# Buck_Converters.net
KiCad netlist of a schematic drawn in Altium Designer
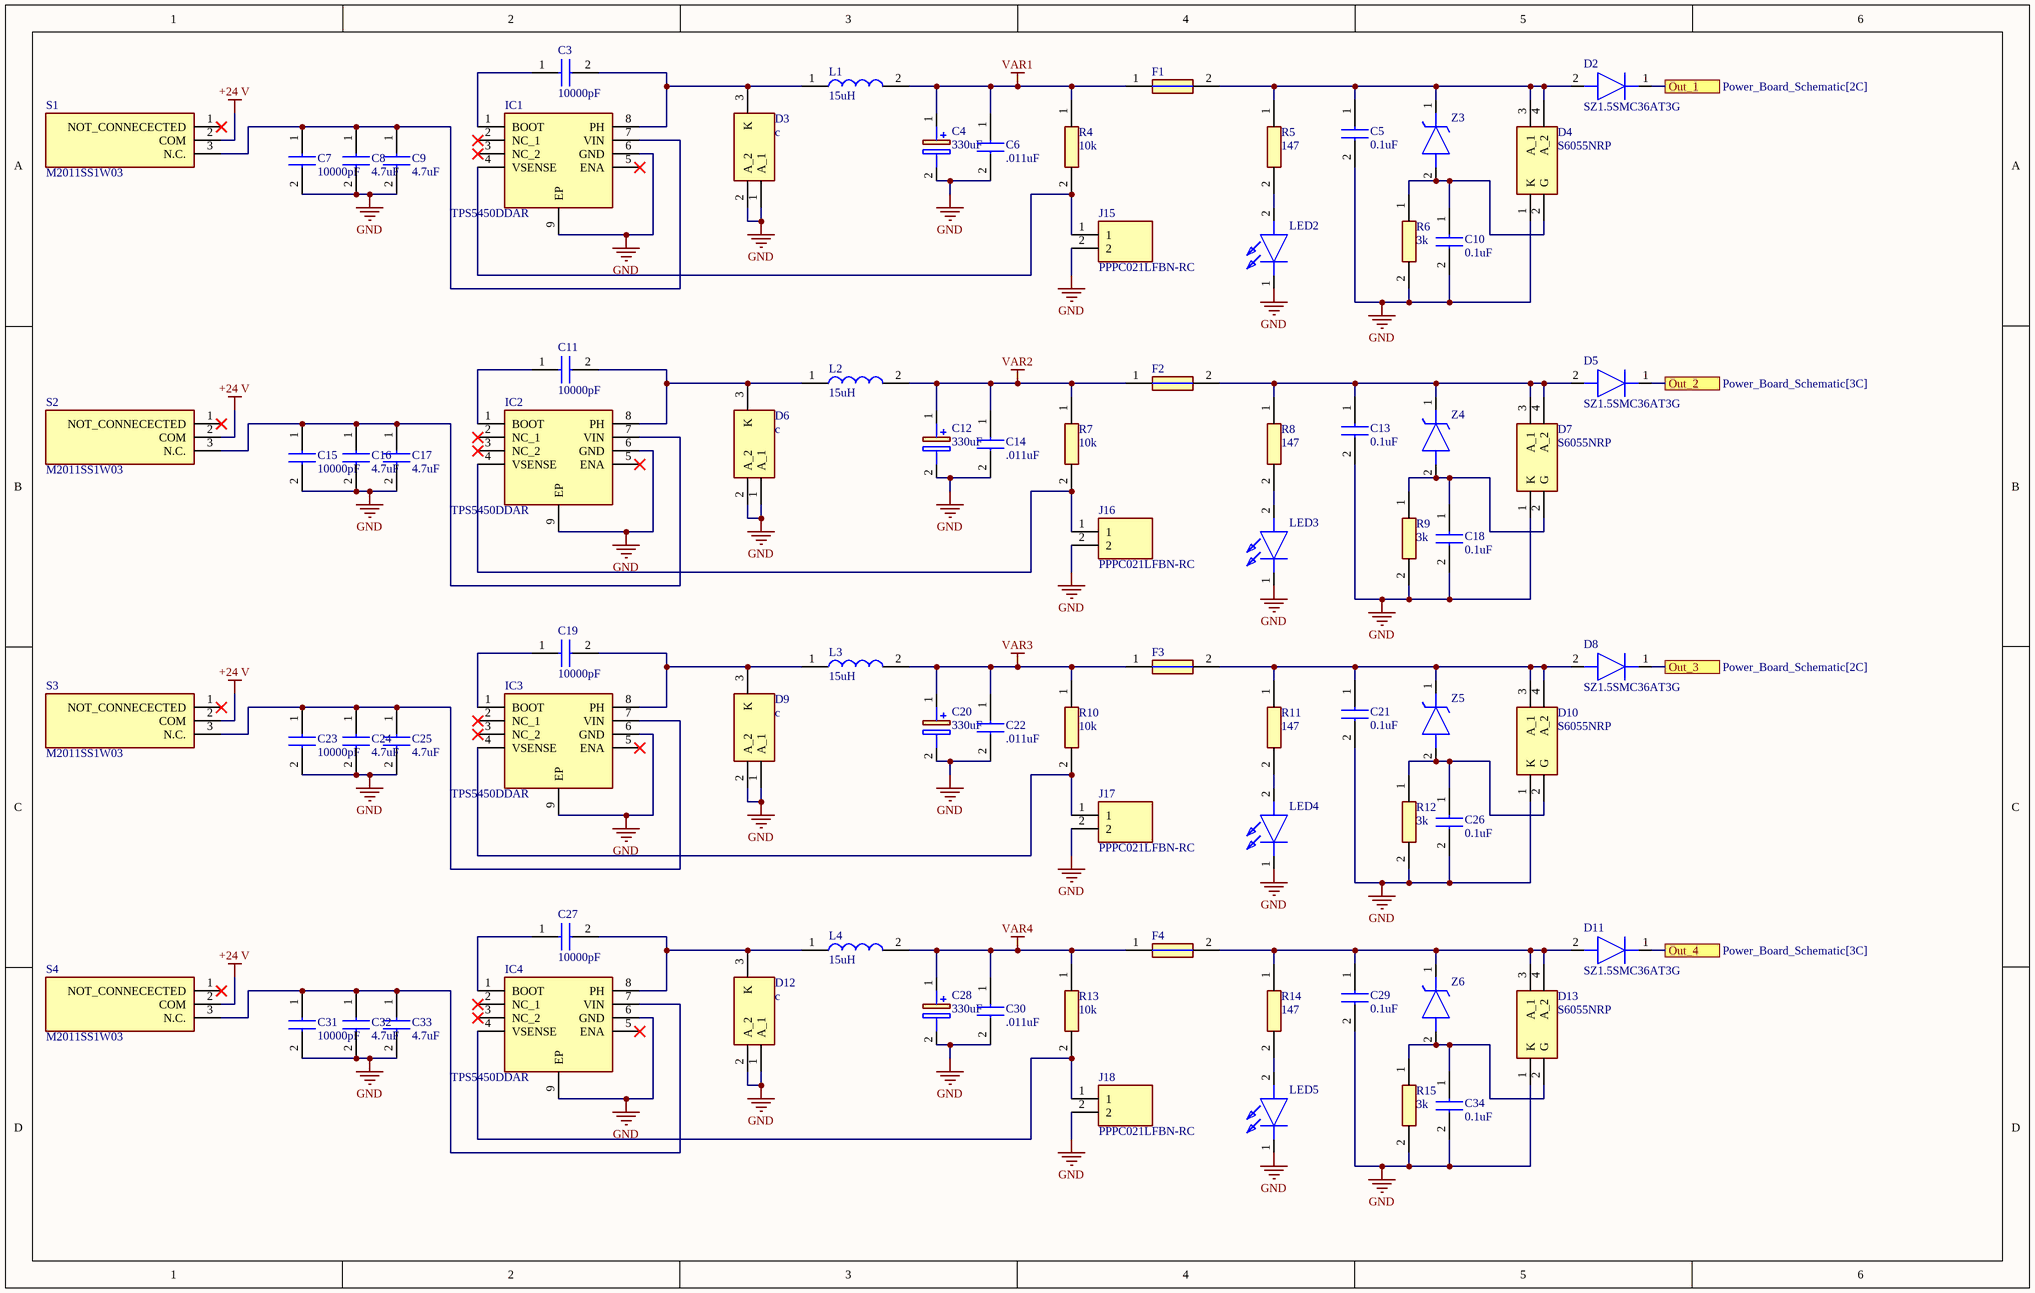
[diagram p0: Buck_Converters.SchDoc]

(export (version "E")
  (design (tool "Eeschema 10.0.6"))
  (components
    (comp (ref "C3")
      (value "10000pF")
      (footprint "SamacSys:CAPC2012X95N")
      (description "Capacitor")
      (fields
        (field (name "MANUFACTURER_PART_NUMBER") "GRM2195C1H103JA01D")
        (field (name "MOUSER PART NUMBER") "81-GRM215C1H103JA01D")
      )
      (libsource (lib "*") (part "GRM2195C1H103JA01D"))
    )
    (comp (ref "C4")
      (value "330uF")
      (footprint "SamacSys:T521X")
      (description "Capacitor Polarised")
      (fields
        (field (name "MANUFACTURER_PART_NUMBER") "T521X337M016ATE025")
        (field (name "MOUSER PART NUMBER") "80-T521X337M16ATE25")
      )
      (libsource (lib "*") (part "T521X337M016ATE025"))
    )
    (comp (ref "C5")
      (value "0.1uF")
      (footprint "SamacSys:CAPC3216X190N")
      (description "Capacitor")
      (fields
        (field (name "MANUFACTURER_PART_NUMBER") "UMJ316BB7104KL8T")
        (field (name "MOUSER PART NUMBER") "963-UMJ316BB7104KL8T")
      )
      (libsource (lib "*") (part "UMJ316BB7104KL8T"))
    )
    (comp (ref "C6")
      (value ".011uF")
      (footprint "SamacSys:CAPC3216X95N")
      (description "Capacitor")
      (fields
        (field (name "MANUFACTURER_PART_NUMBER") "GRM3195C1H113JA01D")
        (field (name "MOUSER PART NUMBER") "81-GRM3195C1H113JA1D")
      )
      (libsource (lib "*") (part "GRM3195C1H113JA01D"))
    )
    (comp (ref "C7")
      (value "10000pF")
      (footprint "SamacSys:CAPC2012X95N")
      (description "Capacitor")
      (fields
        (field (name "MANUFACTURER_PART_NUMBER") "GRM2195C1H103JA01D")
        (field (name "MOUSER PART NUMBER") "81-GRM215C1H103JA01D")
      )
      (libsource (lib "*") (part "GRM2195C1H103JA01D"))
    )
    (comp (ref "C8")
      (value "4.7uF")
      (footprint "SamacSys:CAPC3216X180N")
      (description "Capacitor")
      (fields
        (field (name "MANUFACTURER_PART_NUMBER") "GRM31CR71H475KA12L")
        (field (name "MOUSER PART NUMBER") "81-GRM31CR71H475KA2L")
      )
      (libsource (lib "*") (part "GRM31CR71H475KA12L"))
    )
    (comp (ref "C9")
      (value "4.7uF")
      (footprint "SamacSys:CAPC3216X180N")
      (description "Capacitor")
      (fields
        (field (name "MANUFACTURER_PART_NUMBER") "GRM31CR71H475KA12L")
        (field (name "MOUSER PART NUMBER") "81-GRM31CR71H475KA2L")
      )
      (libsource (lib "*") (part "GRM31CR71H475KA12L"))
    )
    (comp (ref "C10")
      (value "0.1uF")
      (footprint "SamacSys:CAPC3216X190N")
      (description "Capacitor")
      (fields
        (field (name "MANUFACTURER_PART_NUMBER") "UMJ316BB7104KL8T")
        (field (name "MOUSER PART NUMBER") "963-UMJ316BB7104KL8T")
      )
      (libsource (lib "*") (part "UMJ316BB7104KL8T"))
    )
    (comp (ref "C11")
      (value "10000pF")
      (footprint "SamacSys:CAPC2012X95N")
      (description "Capacitor")
      (fields
        (field (name "MANUFACTURER_PART_NUMBER") "GRM2195C1H103JA01D")
        (field (name "MOUSER PART NUMBER") "81-GRM215C1H103JA01D")
      )
      (libsource (lib "*") (part "GRM2195C1H103JA01D"))
    )
    (comp (ref "C12")
      (value "330uF")
      (footprint "SamacSys:T521X")
      (description "Capacitor Polarised")
      (fields
        (field (name "MANUFACTURER_PART_NUMBER") "T521X337M016ATE025")
        (field (name "MOUSER PART NUMBER") "80-T521X337M16ATE25")
      )
      (libsource (lib "*") (part "T521X337M016ATE025"))
    )
    (comp (ref "C13")
      (value "0.1uF")
      (footprint "SamacSys:CAPC3216X190N")
      (description "Capacitor")
      (fields
        (field (name "MANUFACTURER_PART_NUMBER") "UMJ316BB7104KL8T")
        (field (name "MOUSER PART NUMBER") "963-UMJ316BB7104KL8T")
      )
      (libsource (lib "*") (part "UMJ316BB7104KL8T"))
    )
    (comp (ref "C14")
      (value ".011uF")
      (footprint "SamacSys:CAPC3216X95N")
      (description "Capacitor")
      (fields
        (field (name "MANUFACTURER_PART_NUMBER") "GRM3195C1H113JA01D")
        (field (name "MOUSER PART NUMBER") "81-GRM3195C1H113JA1D")
      )
      (libsource (lib "*") (part "GRM3195C1H113JA01D"))
    )
    (comp (ref "C15")
      (value "10000pF")
      (footprint "SamacSys:CAPC2012X95N")
      (description "Capacitor")
      (fields
        (field (name "MANUFACTURER_PART_NUMBER") "GRM2195C1H103JA01D")
        (field (name "MOUSER PART NUMBER") "81-GRM215C1H103JA01D")
      )
      (libsource (lib "*") (part "GRM2195C1H103JA01D"))
    )
    (comp (ref "C16")
      (value "4.7uF")
      (footprint "SamacSys:CAPC3216X180N")
      (description "Capacitor")
      (fields
        (field (name "MANUFACTURER_PART_NUMBER") "GRM31CR71H475KA12L")
        (field (name "MOUSER PART NUMBER") "81-GRM31CR71H475KA2L")
      )
      (libsource (lib "*") (part "GRM31CR71H475KA12L"))
    )
    (comp (ref "C17")
      (value "4.7uF")
      (footprint "SamacSys:CAPC3216X180N")
      (description "Capacitor")
      (fields
        (field (name "MANUFACTURER_PART_NUMBER") "GRM31CR71H475KA12L")
        (field (name "MOUSER PART NUMBER") "81-GRM31CR71H475KA2L")
      )
      (libsource (lib "*") (part "GRM31CR71H475KA12L"))
    )
    (comp (ref "C18")
      (value "0.1uF")
      (footprint "SamacSys:CAPC3216X190N")
      (description "Capacitor")
      (fields
        (field (name "MANUFACTURER_PART_NUMBER") "UMJ316BB7104KL8T")
        (field (name "MOUSER PART NUMBER") "963-UMJ316BB7104KL8T")
      )
      (libsource (lib "*") (part "UMJ316BB7104KL8T"))
    )
    (comp (ref "C19")
      (value "10000pF")
      (footprint "SamacSys:CAPC2012X95N")
      (description "Capacitor")
      (fields
        (field (name "MANUFACTURER_PART_NUMBER") "GRM2195C1H103JA01D")
        (field (name "MOUSER PART NUMBER") "81-GRM215C1H103JA01D")
      )
      (libsource (lib "*") (part "GRM2195C1H103JA01D"))
    )
    (comp (ref "C20")
      (value "330uF")
      (footprint "SamacSys:T521X")
      (description "Capacitor Polarised")
      (fields
        (field (name "MANUFACTURER_PART_NUMBER") "T521X337M016ATE025")
        (field (name "MOUSER PART NUMBER") "80-T521X337M16ATE25")
      )
      (libsource (lib "*") (part "T521X337M016ATE025"))
    )
    (comp (ref "C21")
      (value "0.1uF")
      (footprint "SamacSys:CAPC3216X190N")
      (description "Capacitor")
      (fields
        (field (name "MANUFACTURER_PART_NUMBER") "UMJ316BB7104KL8T")
        (field (name "MOUSER PART NUMBER") "963-UMJ316BB7104KL8T")
      )
      (libsource (lib "*") (part "UMJ316BB7104KL8T"))
    )
    (comp (ref "C22")
      (value ".011uF")
      (footprint "SamacSys:CAPC3216X95N")
      (description "Capacitor")
      (fields
        (field (name "MANUFACTURER_PART_NUMBER") "GRM3195C1H113JA01D")
        (field (name "MOUSER PART NUMBER") "81-GRM3195C1H113JA1D")
      )
      (libsource (lib "*") (part "GRM3195C1H113JA01D"))
    )
    (comp (ref "C23")
      (value "10000pF")
      (footprint "SamacSys:CAPC2012X95N")
      (description "Capacitor")
      (fields
        (field (name "MANUFACTURER_PART_NUMBER") "GRM2195C1H103JA01D")
        (field (name "MOUSER PART NUMBER") "81-GRM215C1H103JA01D")
      )
      (libsource (lib "*") (part "GRM2195C1H103JA01D"))
    )
    (comp (ref "C24")
      (value "4.7uF")
      (footprint "SamacSys:CAPC3216X180N")
      (description "Capacitor")
      (fields
        (field (name "MANUFACTURER_PART_NUMBER") "GRM31CR71H475KA12L")
        (field (name "MOUSER PART NUMBER") "81-GRM31CR71H475KA2L")
      )
      (libsource (lib "*") (part "GRM31CR71H475KA12L"))
    )
    (comp (ref "C25")
      (value "4.7uF")
      (footprint "SamacSys:CAPC3216X180N")
      (description "Capacitor")
      (fields
        (field (name "MANUFACTURER_PART_NUMBER") "GRM31CR71H475KA12L")
        (field (name "MOUSER PART NUMBER") "81-GRM31CR71H475KA2L")
      )
      (libsource (lib "*") (part "GRM31CR71H475KA12L"))
    )
    (comp (ref "C26")
      (value "0.1uF")
      (footprint "SamacSys:CAPC3216X190N")
      (description "Capacitor")
      (fields
        (field (name "MANUFACTURER_PART_NUMBER") "UMJ316BB7104KL8T")
        (field (name "MOUSER PART NUMBER") "963-UMJ316BB7104KL8T")
      )
      (libsource (lib "*") (part "UMJ316BB7104KL8T"))
    )
    (comp (ref "C27")
      (value "10000pF")
      (footprint "SamacSys:CAPC2012X95N")
      (description "Capacitor")
      (fields
        (field (name "MANUFACTURER_PART_NUMBER") "GRM2195C1H103JA01D")
        (field (name "MOUSER PART NUMBER") "81-GRM215C1H103JA01D")
      )
      (libsource (lib "*") (part "GRM2195C1H103JA01D"))
    )
    (comp (ref "C28")
      (value "330uF")
      (footprint "SamacSys:T521X")
      (description "Capacitor Polarised")
      (fields
        (field (name "MANUFACTURER_PART_NUMBER") "T521X337M016ATE025")
        (field (name "MOUSER PART NUMBER") "80-T521X337M16ATE25")
      )
      (libsource (lib "*") (part "T521X337M016ATE025"))
    )
    (comp (ref "C29")
      (value "0.1uF")
      (footprint "SamacSys:CAPC3216X190N")
      (description "Capacitor")
      (fields
        (field (name "MANUFACTURER_PART_NUMBER") "UMJ316BB7104KL8T")
        (field (name "MOUSER PART NUMBER") "963-UMJ316BB7104KL8T")
      )
      (libsource (lib "*") (part "UMJ316BB7104KL8T"))
    )
    (comp (ref "C30")
      (value ".011uF")
      (footprint "SamacSys:CAPC3216X95N")
      (description "Capacitor")
      (fields
        (field (name "MANUFACTURER_PART_NUMBER") "GRM3195C1H113JA01D")
        (field (name "MOUSER PART NUMBER") "81-GRM3195C1H113JA1D")
      )
      (libsource (lib "*") (part "GRM3195C1H113JA01D"))
    )
    (comp (ref "C31")
      (value "10000pF")
      (footprint "SamacSys:CAPC2012X95N")
      (description "Capacitor")
      (fields
        (field (name "MANUFACTURER_PART_NUMBER") "GRM2195C1H103JA01D")
        (field (name "MOUSER PART NUMBER") "81-GRM215C1H103JA01D")
      )
      (libsource (lib "*") (part "GRM2195C1H103JA01D"))
    )
    (comp (ref "C32")
      (value "4.7uF")
      (footprint "SamacSys:CAPC3216X180N")
      (description "Capacitor")
      (fields
        (field (name "MANUFACTURER_PART_NUMBER") "GRM31CR71H475KA12L")
        (field (name "MOUSER PART NUMBER") "81-GRM31CR71H475KA2L")
      )
      (libsource (lib "*") (part "GRM31CR71H475KA12L"))
    )
    (comp (ref "C33")
      (value "4.7uF")
      (footprint "SamacSys:CAPC3216X180N")
      (description "Capacitor")
      (fields
        (field (name "MANUFACTURER_PART_NUMBER") "GRM31CR71H475KA12L")
        (field (name "MOUSER PART NUMBER") "81-GRM31CR71H475KA2L")
      )
      (libsource (lib "*") (part "GRM31CR71H475KA12L"))
    )
    (comp (ref "C34")
      (value "0.1uF")
      (footprint "SamacSys:CAPC3216X190N")
      (description "Capacitor")
      (fields
        (field (name "MANUFACTURER_PART_NUMBER") "UMJ316BB7104KL8T")
        (field (name "MOUSER PART NUMBER") "963-UMJ316BB7104KL8T")
      )
      (libsource (lib "*") (part "UMJ316BB7104KL8T"))
    )
    (comp (ref "D2")
      (value "SZ1.5SMC36AT3G")
      (footprint "SamacSys:DIOM7958X256N")
      (description "Diode")
      (fields (field (name "MOUSER PART NUMBER") "863-SZ1.5SMC36AT3G"))
      (libsource (lib "SamacSys") (part "SZ1.5SMC36AT3G"))
    )
    (comp (ref "D3")
      (value "c")
      (footprint "SamacSys:PMEG045T100EPEZ")
      (description "Schottky Diode")
      (fields
        (field (name "MANUFACTURER_PART_NUMBER") "PMEG045T100EPEZ")
        (field (name "MOUSER PART NUMBER") "771-PMEG045T100EPEZ")
      )
      (libsource (lib "*") (part "PMEG045T100EPEZ"))
    )
    (comp (ref "D4")
      (value "S6055NRP")
      (footprint "SamacSys:S6055NRP")
      (description "SCR")
      (fields (field (name "MOUSER PART NUMBER") "576-S6055NRP"))
      (libsource (lib "*") (part "S6055NRP"))
    )
    (comp (ref "D5")
      (value "SZ1.5SMC36AT3G")
      (footprint "SamacSys:DIOM7958X256N")
      (description "Diode")
      (fields (field (name "MOUSER PART NUMBER") "863-SZ1.5SMC36AT3G"))
      (libsource (lib "SamacSys") (part "SZ1.5SMC36AT3G"))
    )
    (comp (ref "D6")
      (value "c")
      (footprint "SamacSys:PMEG045T100EPEZ")
      (description "Schottky Diode")
      (fields
        (field (name "MANUFACTURER_PART_NUMBER") "PMEG045T100EPEZ")
        (field (name "MOUSER PART NUMBER") "771-PMEG045T100EPEZ")
      )
      (libsource (lib "*") (part "PMEG045T100EPEZ"))
    )
    (comp (ref "D7")
      (value "S6055NRP")
      (footprint "SamacSys:S6055NRP")
      (description "SCR")
      (fields (field (name "MOUSER PART NUMBER") "576-S6055NRP"))
      (libsource (lib "*") (part "S6055NRP"))
    )
    (comp (ref "D8")
      (value "SZ1.5SMC36AT3G")
      (footprint "SamacSys:DIOM7958X256N")
      (description "Diode")
      (fields (field (name "MOUSER PART NUMBER") "863-SZ1.5SMC36AT3G"))
      (libsource (lib "SamacSys") (part "SZ1.5SMC36AT3G"))
    )
    (comp (ref "D9")
      (value "c")
      (footprint "SamacSys:PMEG045T100EPEZ")
      (description "Schottky Diode")
      (fields
        (field (name "MANUFACTURER_PART_NUMBER") "PMEG045T100EPEZ")
        (field (name "MOUSER PART NUMBER") "771-PMEG045T100EPEZ")
      )
      (libsource (lib "*") (part "PMEG045T100EPEZ"))
    )
    (comp (ref "D10")
      (value "S6055NRP")
      (footprint "SamacSys:S6055NRP")
      (description "SCR")
      (fields (field (name "MOUSER PART NUMBER") "576-S6055NRP"))
      (libsource (lib "*") (part "S6055NRP"))
    )
    (comp (ref "D11")
      (value "SZ1.5SMC36AT3G")
      (footprint "SamacSys:DIOM7958X256N")
      (description "Diode")
      (fields (field (name "MOUSER PART NUMBER") "863-SZ1.5SMC36AT3G"))
      (libsource (lib "SamacSys") (part "SZ1.5SMC36AT3G"))
    )
    (comp (ref "D12")
      (value "c")
      (footprint "SamacSys:PMEG045T100EPEZ")
      (description "Schottky Diode")
      (fields
        (field (name "MANUFACTURER_PART_NUMBER") "PMEG045T100EPEZ")
        (field (name "MOUSER PART NUMBER") "771-PMEG045T100EPEZ")
      )
      (libsource (lib "*") (part "PMEG045T100EPEZ"))
    )
    (comp (ref "D13")
      (value "S6055NRP")
      (footprint "SamacSys:S6055NRP")
      (description "SCR")
      (fields (field (name "MOUSER PART NUMBER") "576-S6055NRP"))
      (libsource (lib "*") (part "S6055NRP"))
    )
    (comp (ref "F1")
      (value "MFU0805FF05000P100")
      (footprint "SamacSys:FUSC2012X55N")
      (description "Fuse")
      (fields (field (name "MOUSER PART NUMBER") "594-MFU0805FF05000P1"))
      (libsource (lib "*") (part "MFU0805FF05000P100"))
    )
    (comp (ref "F2")
      (value "MFU0805FF05000P100")
      (footprint "SamacSys:FUSC2012X55N")
      (description "Fuse")
      (fields (field (name "MOUSER PART NUMBER") "594-MFU0805FF05000P1"))
      (libsource (lib "*") (part "MFU0805FF05000P100"))
    )
    (comp (ref "F3")
      (value "MFU0805FF05000P100")
      (footprint "SamacSys:FUSC2012X55N")
      (description "Fuse")
      (fields (field (name "MOUSER PART NUMBER") "594-MFU0805FF05000P1"))
      (libsource (lib "*") (part "MFU0805FF05000P100"))
    )
    (comp (ref "F4")
      (value "MFU0805FF05000P100")
      (footprint "SamacSys:FUSC2012X55N")
      (description "Fuse")
      (fields (field (name "MOUSER PART NUMBER") "594-MFU0805FF05000P1"))
      (libsource (lib "*") (part "MFU0805FF05000P100"))
    )
    (comp (ref "IC1")
      (value "TPS5450DDAR")
      (footprint "SamacSys:SOIC127P600X170-9N")
      (description "Integrated Circuit")
      (fields (field (name "MOUSER PART NUMBER") "595-TPS5450DDAR"))
      (libsource (lib "*") (part "TPS5450DDAR"))
    )
    (comp (ref "IC2")
      (value "TPS5450DDAR")
      (footprint "SamacSys:SOIC127P600X170-9N")
      (description "Integrated Circuit")
      (fields (field (name "MOUSER PART NUMBER") "595-TPS5450DDAR"))
      (libsource (lib "*") (part "TPS5450DDAR"))
    )
    (comp (ref "IC3")
      (value "TPS5450DDAR")
      (footprint "SamacSys:SOIC127P600X170-9N")
      (description "Integrated Circuit")
      (fields (field (name "MOUSER PART NUMBER") "595-TPS5450DDAR"))
      (libsource (lib "*") (part "TPS5450DDAR"))
    )
    (comp (ref "IC4")
      (value "TPS5450DDAR")
      (footprint "SamacSys:SOIC127P600X170-9N")
      (description "Integrated Circuit")
      (fields (field (name "MOUSER PART NUMBER") "595-TPS5450DDAR"))
      (libsource (lib "*") (part "TPS5450DDAR"))
    )
    (comp (ref "J15")
      (value "PPPC021LFBN-RC")
      (footprint "SamacSys:RHDR2W80P0X254_1X2_558X254X850P")
      (description "Connector")
      (libsource (lib "*") (part "PPPC021LFBN-RC"))
    )
    (comp (ref "J16")
      (value "PPPC021LFBN-RC")
      (footprint "SamacSys:RHDR2W80P0X254_1X2_558X254X850P")
      (description "Connector")
      (libsource (lib "*") (part "PPPC021LFBN-RC"))
    )
    (comp (ref "J17")
      (value "PPPC021LFBN-RC")
      (footprint "SamacSys:RHDR2W80P0X254_1X2_558X254X850P")
      (description "Connector")
      (libsource (lib "*") (part "PPPC021LFBN-RC"))
    )
    (comp (ref "J18")
      (value "PPPC021LFBN-RC")
      (footprint "SamacSys:RHDR2W80P0X254_1X2_558X254X850P")
      (description "Connector")
      (libsource (lib "*") (part "PPPC021LFBN-RC"))
    )
    (comp (ref "L1")
      (value "15uH")
      (footprint "SamacSys:WE-PD_1260/1245/1280/121054")
      (description "Inductor")
      (fields
        (field (name "MANUFACTURER_PART_NUMBER") "7447709150")
        (field (name "MOUSER PART NUMBER") "710-7447709150")
      )
      (libsource (lib "*") (part "7447709150"))
    )
    (comp (ref "L2")
      (value "15uH")
      (footprint "SamacSys:WE-PD_1260/1245/1280/121054")
      (description "Inductor")
      (fields
        (field (name "MANUFACTURER_PART_NUMBER") "7447709150")
        (field (name "MOUSER PART NUMBER") "710-7447709150")
      )
      (libsource (lib "*") (part "7447709150"))
    )
    (comp (ref "L3")
      (value "15uH")
      (footprint "SamacSys:WE-PD_1260/1245/1280/121054")
      (description "Inductor")
      (fields
        (field (name "MANUFACTURER_PART_NUMBER") "7447709150")
        (field (name "MOUSER PART NUMBER") "710-7447709150")
      )
      (libsource (lib "*") (part "7447709150"))
    )
    (comp (ref "L4")
      (value "15uH")
      (footprint "SamacSys:WE-PD_1260/1245/1280/121054")
      (description "Inductor")
      (fields
        (field (name "MANUFACTURER_PART_NUMBER") "7447709150")
        (field (name "MOUSER PART NUMBER") "710-7447709150")
      )
      (libsource (lib "*") (part "7447709150"))
    )
    (comp (ref "LED2")
      (value "CMD15-21VYC_TR8")
      (footprint "SamacSys:LEDC3215X130N")
      (description "LED")
      (fields
        (field (name "MANUFACTURER_PART_NUMBER") "CMD15-21VYC/TR8")
        (field (name "MOUSER PART NUMBER") "606-CMD15-21VYC")
      )
      (libsource (lib "*") (part "CMD15-21VYC_TR8"))
    )
    (comp (ref "LED3")
      (value "CMD15-21VYC_TR8")
      (footprint "SamacSys:LEDC3215X130N")
      (description "LED")
      (fields
        (field (name "MANUFACTURER_PART_NUMBER") "CMD15-21VYC/TR8")
        (field (name "MOUSER PART NUMBER") "606-CMD15-21VYC")
      )
      (libsource (lib "*") (part "CMD15-21VYC_TR8"))
    )
    (comp (ref "LED4")
      (value "CMD15-21VYC_TR8")
      (footprint "SamacSys:LEDC3215X130N")
      (description "LED")
      (fields
        (field (name "MANUFACTURER_PART_NUMBER") "CMD15-21VYC/TR8")
        (field (name "MOUSER PART NUMBER") "606-CMD15-21VYC")
      )
      (libsource (lib "*") (part "CMD15-21VYC_TR8"))
    )
    (comp (ref "LED5")
      (value "CMD15-21VYC_TR8")
      (footprint "SamacSys:LEDC3215X130N")
      (description "LED")
      (fields
        (field (name "MANUFACTURER_PART_NUMBER") "CMD15-21VYC/TR8")
        (field (name "MOUSER PART NUMBER") "606-CMD15-21VYC")
      )
      (libsource (lib "*") (part "CMD15-21VYC_TR8"))
    )
    (comp (ref "R4")
      (value "10k")
      (footprint "SamacSys:ERJP08_(1206)")
      (description "Resistor")
      (fields
        (field (name "MANUFACTURER_PART_NUMBER") "ERJ-P08J103V")
        (field (name "MOUSER PART NUMBER") "667-ERJ-P08J103V")
      )
      (libsource (lib "*") (part "ERJ-P08J103V"))
    )
    (comp (ref "R5")
      (value "147")
      (footprint "SamacSys:RESC3216X70N")
      (description "Resistor")
      (fields (field (name "MANUFACTURER_PART_NUMBER") "RK73H2BTTD1470F"))
      (libsource (lib "*") (part "RK73H2BTTD1470F"))
    )
    (comp (ref "R6")
      (value "3k")
      (footprint "SamacSys:ERJP08_(1206)")
      (description "Resistor")
      (fields
        (field (name "MANUFACTURER_PART_NUMBER") "ERJ-P08J302V")
        (field (name "MOUSER PART NUMBER") "667-ERJ-P08J302V")
      )
      (libsource (lib "*") (part "ERJ-P08J302V"))
    )
    (comp (ref "R7")
      (value "10k")
      (footprint "SamacSys:ERJP08_(1206)")
      (description "Resistor")
      (fields
        (field (name "MANUFACTURER_PART_NUMBER") "ERJ-P08J103V")
        (field (name "MOUSER PART NUMBER") "667-ERJ-P08J103V")
      )
      (libsource (lib "*") (part "ERJ-P08J103V"))
    )
    (comp (ref "R8")
      (value "147")
      (footprint "SamacSys:RESC3216X70N")
      (description "Resistor")
      (fields (field (name "MANUFACTURER_PART_NUMBER") "RK73H2BTTD1470F"))
      (libsource (lib "*") (part "RK73H2BTTD1470F"))
    )
    (comp (ref "R9")
      (value "3k")
      (footprint "SamacSys:ERJP08_(1206)")
      (description "Resistor")
      (fields
        (field (name "MANUFACTURER_PART_NUMBER") "ERJ-P08J302V")
        (field (name "MOUSER PART NUMBER") "667-ERJ-P08J302V")
      )
      (libsource (lib "*") (part "ERJ-P08J302V"))
    )
    (comp (ref "R10")
      (value "10k")
      (footprint "SamacSys:ERJP08_(1206)")
      (description "Resistor")
      (fields
        (field (name "MANUFACTURER_PART_NUMBER") "ERJ-P08J103V")
        (field (name "MOUSER PART NUMBER") "667-ERJ-P08J103V")
      )
      (libsource (lib "*") (part "ERJ-P08J103V"))
    )
    (comp (ref "R11")
      (value "147")
      (footprint "SamacSys:RESC3216X70N")
      (description "Resistor")
      (fields (field (name "MANUFACTURER_PART_NUMBER") "RK73H2BTTD1470F"))
      (libsource (lib "*") (part "RK73H2BTTD1470F"))
    )
    (comp (ref "R12")
      (value "3k")
      (footprint "SamacSys:ERJP08_(1206)")
      (description "Resistor")
      (fields
        (field (name "MANUFACTURER_PART_NUMBER") "ERJ-P08J302V")
        (field (name "MOUSER PART NUMBER") "667-ERJ-P08J302V")
      )
      (libsource (lib "*") (part "ERJ-P08J302V"))
    )
    (comp (ref "R13")
      (value "10k")
      (footprint "SamacSys:ERJP08_(1206)")
      (description "Resistor")
      (fields
        (field (name "MANUFACTURER_PART_NUMBER") "ERJ-P08J103V")
        (field (name "MOUSER PART NUMBER") "667-ERJ-P08J103V")
      )
      (libsource (lib "*") (part "ERJ-P08J103V"))
    )
    (comp (ref "R14")
      (value "147")
      (footprint "SamacSys:RESC3216X70N")
      (description "Resistor")
      (fields (field (name "MANUFACTURER_PART_NUMBER") "RK73H2BTTD1470F"))
      (libsource (lib "*") (part "RK73H2BTTD1470F"))
    )
    (comp (ref "R15")
      (value "3k")
      (footprint "SamacSys:ERJP08_(1206)")
      (description "Resistor")
      (fields
        (field (name "MANUFACTURER_PART_NUMBER") "ERJ-P08J302V")
        (field (name "MOUSER PART NUMBER") "667-ERJ-P08J302V")
      )
      (libsource (lib "*") (part "ERJ-P08J302V"))
    )
    (comp (ref "S1")
      (value "M2011SS1W03")
      (footprint "SamacSys:M2011SS1W03")
      (description "Switch")
      (fields (field (name "MOUSER PART NUMBER") "633-M2011SS1W03"))
      (libsource (lib "*") (part "M2011SS1W03"))
    )
    (comp (ref "S2")
      (value "M2011SS1W03")
      (footprint "SamacSys:M2011SS1W03")
      (description "Switch")
      (fields (field (name "MOUSER PART NUMBER") "633-M2011SS1W03"))
      (libsource (lib "*") (part "M2011SS1W03"))
    )
    (comp (ref "S3")
      (value "M2011SS1W03")
      (footprint "SamacSys:M2011SS1W03")
      (description "Switch")
      (fields (field (name "MOUSER PART NUMBER") "633-M2011SS1W03"))
      (libsource (lib "*") (part "M2011SS1W03"))
    )
    (comp (ref "S4")
      (value "M2011SS1W03")
      (footprint "SamacSys:M2011SS1W03")
      (description "Switch")
      (fields (field (name "MOUSER PART NUMBER") "633-M2011SS1W03"))
      (libsource (lib "*") (part "M2011SS1W03"))
    )
    (comp (ref "Z3")
      (value "SMBJ5352B-TP")
      (footprint "SamacSys:DIOM5336X262N")
      (description "Zener Diode")
      (fields (field (name "MOUSER PART NUMBER") "833-SMBJ5352B-TP"))
      (libsource (lib "*") (part "SMBJ5352B-TP"))
    )
    (comp (ref "Z4")
      (value "SMBJ5352B-TP")
      (footprint "SamacSys:DIOM5336X262N")
      (description "Zener Diode")
      (fields (field (name "MOUSER PART NUMBER") "833-SMBJ5352B-TP"))
      (libsource (lib "*") (part "SMBJ5352B-TP"))
    )
    (comp (ref "Z5")
      (value "SMBJ5352B-TP")
      (footprint "SamacSys:DIOM5336X262N")
      (description "Zener Diode")
      (fields (field (name "MOUSER PART NUMBER") "833-SMBJ5352B-TP"))
      (libsource (lib "*") (part "SMBJ5352B-TP"))
    )
    (comp (ref "Z6")
      (value "SMBJ5352B-TP")
      (footprint "SamacSys:DIOM5336X262N")
      (description "Zener Diode")
      (fields (field (name "MOUSER PART NUMBER") "833-SMBJ5352B-TP"))
      (libsource (lib "*") (part "SMBJ5352B-TP"))
    )
  )
  (nets
    (net (code "1") (name "+24 V") (class "Default")
      (node (ref "S1") (pin "2") (pinfunction "COM_2") (pintype "passive"))
      (node (ref "S2") (pin "2") (pinfunction "COM_2") (pintype "passive"))
      (node (ref "S3") (pin "2") (pinfunction "COM_2") (pintype "passive"))
      (node (ref "S4") (pin "2") (pinfunction "COM_2") (pintype "passive"))
    )
    (net (code "2") (name "/Out_1") (class "Default")
      (node (ref "D2") (pin "1") (pinfunction "K_1") (pintype "passive"))
    )
    (net (code "3") (name "/Out_2") (class "Default")
      (node (ref "D5") (pin "1") (pinfunction "K_1") (pintype "passive"))
    )
    (net (code "4") (name "/Out_3") (class "Default")
      (node (ref "D8") (pin "1") (pinfunction "K_1") (pintype "passive"))
    )
    (net (code "5") (name "/Out_4") (class "Default")
      (node (ref "D11") (pin "1") (pinfunction "K_1") (pintype "passive"))
    )
    (net (code "6") (name "GND") (class "Default")
      (node (ref "C10") (pin "2") (pinfunction "2_2") (pintype "passive"))
      (node (ref "C12") (pin "2") (pinfunction "-_2") (pintype "passive"))
      (node (ref "C13") (pin "2") (pinfunction "2_2") (pintype "passive"))
      (node (ref "C14") (pin "2") (pinfunction "2_2") (pintype "passive"))
      (node (ref "C15") (pin "2") (pinfunction "2_2") (pintype "passive"))
      (node (ref "C16") (pin "2") (pinfunction "2_2") (pintype "passive"))
      (node (ref "C17") (pin "2") (pinfunction "2_2") (pintype "passive"))
      (node (ref "C18") (pin "2") (pinfunction "2_2") (pintype "passive"))
      (node (ref "C20") (pin "2") (pinfunction "-_2") (pintype "passive"))
      (node (ref "C21") (pin "2") (pinfunction "2_2") (pintype "passive"))
      (node (ref "C22") (pin "2") (pinfunction "2_2") (pintype "passive"))
      (node (ref "C23") (pin "2") (pinfunction "2_2") (pintype "passive"))
      (node (ref "C24") (pin "2") (pinfunction "2_2") (pintype "passive"))
      (node (ref "C25") (pin "2") (pinfunction "2_2") (pintype "passive"))
      (node (ref "C26") (pin "2") (pinfunction "2_2") (pintype "passive"))
      (node (ref "C28") (pin "2") (pinfunction "-_2") (pintype "passive"))
      (node (ref "C29") (pin "2") (pinfunction "2_2") (pintype "passive"))
      (node (ref "C30") (pin "2") (pinfunction "2_2") (pintype "passive"))
      (node (ref "C31") (pin "2") (pinfunction "2_2") (pintype "passive"))
      (node (ref "C32") (pin "2") (pinfunction "2_2") (pintype "passive"))
      (node (ref "C33") (pin "2") (pinfunction "2_2") (pintype "passive"))
      (node (ref "C34") (pin "2") (pinfunction "2_2") (pintype "passive"))
      (node (ref "C4") (pin "2") (pinfunction "-_2") (pintype "passive"))
      (node (ref "C5") (pin "2") (pinfunction "2_2") (pintype "passive"))
      (node (ref "C6") (pin "2") (pinfunction "2_2") (pintype "passive"))
      (node (ref "C7") (pin "2") (pinfunction "2_2") (pintype "passive"))
      (node (ref "C8") (pin "2") (pinfunction "2_2") (pintype "passive"))
      (node (ref "C9") (pin "2") (pinfunction "2_2") (pintype "passive"))
      (node (ref "D10") (pin "1") (pinfunction "K_1") (pintype "passive"))
      (node (ref "D12") (pin "1") (pinfunction "A_1_1") (pintype "passive"))
      (node (ref "D12") (pin "2") (pinfunction "A_2_2") (pintype "passive"))
      (node (ref "D13") (pin "1") (pinfunction "K_1") (pintype "passive"))
      (node (ref "D3") (pin "1") (pinfunction "A_1_1") (pintype "passive"))
      (node (ref "D3") (pin "2") (pinfunction "A_2_2") (pintype "passive"))
      (node (ref "D4") (pin "1") (pinfunction "K_1") (pintype "passive"))
      (node (ref "D6") (pin "1") (pinfunction "A_1_1") (pintype "passive"))
      (node (ref "D6") (pin "2") (pinfunction "A_2_2") (pintype "passive"))
      (node (ref "D7") (pin "1") (pinfunction "K_1") (pintype "passive"))
      (node (ref "D9") (pin "1") (pinfunction "A_1_1") (pintype "passive"))
      (node (ref "D9") (pin "2") (pinfunction "A_2_2") (pintype "passive"))
      (node (ref "IC1") (pin "6") (pinfunction "GND_6") (pintype "passive"))
      (node (ref "IC1") (pin "9") (pinfunction "EP_9") (pintype "passive"))
      (node (ref "IC2") (pin "6") (pinfunction "GND_6") (pintype "passive"))
      (node (ref "IC2") (pin "9") (pinfunction "EP_9") (pintype "passive"))
      (node (ref "IC3") (pin "6") (pinfunction "GND_6") (pintype "passive"))
      (node (ref "IC3") (pin "9") (pinfunction "EP_9") (pintype "passive"))
      (node (ref "IC4") (pin "6") (pinfunction "GND_6") (pintype "passive"))
      (node (ref "IC4") (pin "9") (pinfunction "EP_9") (pintype "passive"))
      (node (ref "J15") (pin "2") (pinfunction "2_2") (pintype "passive"))
      (node (ref "J16") (pin "2") (pinfunction "2_2") (pintype "passive"))
      (node (ref "J17") (pin "2") (pinfunction "2_2") (pintype "passive"))
      (node (ref "J18") (pin "2") (pinfunction "2_2") (pintype "passive"))
      (node (ref "LED2") (pin "1") (pinfunction "K_1") (pintype "passive"))
      (node (ref "LED3") (pin "1") (pinfunction "K_1") (pintype "passive"))
      (node (ref "LED4") (pin "1") (pinfunction "K_1") (pintype "passive"))
      (node (ref "LED5") (pin "1") (pinfunction "K_1") (pintype "passive"))
      (node (ref "R12") (pin "2") (pinfunction "2_2") (pintype "passive"))
      (node (ref "R15") (pin "2") (pinfunction "2_2") (pintype "passive"))
      (node (ref "R6") (pin "2") (pinfunction "2_2") (pintype "passive"))
      (node (ref "R9") (pin "2") (pinfunction "2_2") (pintype "passive"))
    )
    (net (code "7") (name "Net-(D2-A)") (class "Default")
      (node (ref "C5") (pin "1") (pinfunction "1_1") (pintype "passive"))
      (node (ref "D2") (pin "2") (pinfunction "A_2") (pintype "passive"))
      (node (ref "D4") (pin "3") (pinfunction "A_1_3") (pintype "passive"))
      (node (ref "D4") (pin "4") (pinfunction "A_2_4") (pintype "passive"))
      (node (ref "F1") (pin "2") (pinfunction "2_2") (pintype "passive"))
      (node (ref "R5") (pin "1") (pinfunction "1_1") (pintype "passive"))
      (node (ref "Z3") (pin "1") (pinfunction "K_1") (pintype "passive"))
    )
    (net (code "8") (name "Net-(D3-K)") (class "Default")
      (node (ref "C3") (pin "2") (pinfunction "2_2") (pintype "passive"))
      (node (ref "D3") (pin "3") (pinfunction "K_3") (pintype "passive"))
      (node (ref "IC1") (pin "8") (pinfunction "PH_8") (pintype "passive"))
      (node (ref "L1") (pin "1") (pinfunction "1_1") (pintype "passive"))
    )
    (net (code "9") (name "Net-(D4-G)") (class "Default")
      (node (ref "C10") (pin "1") (pinfunction "1_1") (pintype "passive"))
      (node (ref "D4") (pin "2") (pinfunction "G_2") (pintype "passive"))
      (node (ref "R6") (pin "1") (pinfunction "1_1") (pintype "passive"))
      (node (ref "Z3") (pin "2") (pinfunction "A_2") (pintype "passive"))
    )
    (net (code "10") (name "Net-(D5-A)") (class "Default")
      (node (ref "C13") (pin "1") (pinfunction "1_1") (pintype "passive"))
      (node (ref "D5") (pin "2") (pinfunction "A_2") (pintype "passive"))
      (node (ref "D7") (pin "3") (pinfunction "A_1_3") (pintype "passive"))
      (node (ref "D7") (pin "4") (pinfunction "A_2_4") (pintype "passive"))
      (node (ref "F2") (pin "2") (pinfunction "2_2") (pintype "passive"))
      (node (ref "R8") (pin "1") (pinfunction "1_1") (pintype "passive"))
      (node (ref "Z4") (pin "1") (pinfunction "K_1") (pintype "passive"))
    )
    (net (code "11") (name "Net-(D6-K)") (class "Default")
      (node (ref "C11") (pin "2") (pinfunction "2_2") (pintype "passive"))
      (node (ref "D6") (pin "3") (pinfunction "K_3") (pintype "passive"))
      (node (ref "IC2") (pin "8") (pinfunction "PH_8") (pintype "passive"))
      (node (ref "L2") (pin "1") (pinfunction "1_1") (pintype "passive"))
    )
    (net (code "12") (name "Net-(D7-G)") (class "Default")
      (node (ref "C18") (pin "1") (pinfunction "1_1") (pintype "passive"))
      (node (ref "D7") (pin "2") (pinfunction "G_2") (pintype "passive"))
      (node (ref "R9") (pin "1") (pinfunction "1_1") (pintype "passive"))
      (node (ref "Z4") (pin "2") (pinfunction "A_2") (pintype "passive"))
    )
    (net (code "13") (name "Net-(D9-K)") (class "Default")
      (node (ref "C19") (pin "2") (pinfunction "2_2") (pintype "passive"))
      (node (ref "D9") (pin "3") (pinfunction "K_3") (pintype "passive"))
      (node (ref "IC3") (pin "8") (pinfunction "PH_8") (pintype "passive"))
      (node (ref "L3") (pin "1") (pinfunction "1_1") (pintype "passive"))
    )
    (net (code "14") (name "Net-(D10-A_1)") (class "Default")
      (node (ref "C21") (pin "1") (pinfunction "1_1") (pintype "passive"))
      (node (ref "D10") (pin "3") (pinfunction "A_1_3") (pintype "passive"))
      (node (ref "D10") (pin "4") (pinfunction "A_2_4") (pintype "passive"))
      (node (ref "D8") (pin "2") (pinfunction "A_2") (pintype "passive"))
      (node (ref "F3") (pin "2") (pinfunction "2_2") (pintype "passive"))
      (node (ref "R11") (pin "1") (pinfunction "1_1") (pintype "passive"))
      (node (ref "Z5") (pin "1") (pinfunction "K_1") (pintype "passive"))
    )
    (net (code "15") (name "Net-(D10-G)") (class "Default")
      (node (ref "C26") (pin "1") (pinfunction "1_1") (pintype "passive"))
      (node (ref "D10") (pin "2") (pinfunction "G_2") (pintype "passive"))
      (node (ref "R12") (pin "1") (pinfunction "1_1") (pintype "passive"))
      (node (ref "Z5") (pin "2") (pinfunction "A_2") (pintype "passive"))
    )
    (net (code "16") (name "Net-(D11-A)") (class "Default")
      (node (ref "C29") (pin "1") (pinfunction "1_1") (pintype "passive"))
      (node (ref "D11") (pin "2") (pinfunction "A_2") (pintype "passive"))
      (node (ref "D13") (pin "3") (pinfunction "A_1_3") (pintype "passive"))
      (node (ref "D13") (pin "4") (pinfunction "A_2_4") (pintype "passive"))
      (node (ref "F4") (pin "2") (pinfunction "2_2") (pintype "passive"))
      (node (ref "R14") (pin "1") (pinfunction "1_1") (pintype "passive"))
      (node (ref "Z6") (pin "1") (pinfunction "K_1") (pintype "passive"))
    )
    (net (code "17") (name "Net-(D12-K)") (class "Default")
      (node (ref "C27") (pin "2") (pinfunction "2_2") (pintype "passive"))
      (node (ref "D12") (pin "3") (pinfunction "K_3") (pintype "passive"))
      (node (ref "IC4") (pin "8") (pinfunction "PH_8") (pintype "passive"))
      (node (ref "L4") (pin "1") (pinfunction "1_1") (pintype "passive"))
    )
    (net (code "18") (name "Net-(D13-G)") (class "Default")
      (node (ref "C34") (pin "1") (pinfunction "1_1") (pintype "passive"))
      (node (ref "D13") (pin "2") (pinfunction "G_2") (pintype "passive"))
      (node (ref "R15") (pin "1") (pinfunction "1_1") (pintype "passive"))
      (node (ref "Z6") (pin "2") (pinfunction "A_2") (pintype "passive"))
    )
    (net (code "19") (name "Net-(IC1-BOOT)") (class "Default")
      (node (ref "C3") (pin "1") (pinfunction "1_1") (pintype "passive"))
      (node (ref "IC1") (pin "1") (pinfunction "BOOT_1") (pintype "passive"))
    )
    (net (code "20") (name "Net-(IC1-VIN)") (class "Default")
      (node (ref "C7") (pin "1") (pinfunction "1_1") (pintype "passive"))
      (node (ref "C8") (pin "1") (pinfunction "1_1") (pintype "passive"))
      (node (ref "C9") (pin "1") (pinfunction "1_1") (pintype "passive"))
      (node (ref "IC1") (pin "7") (pinfunction "VIN_7") (pintype "passive"))
      (node (ref "S1") (pin "3") (pinfunction "N.C._3") (pintype "passive"))
    )
    (net (code "21") (name "Net-(IC1-VSENSE)") (class "Default")
      (node (ref "IC1") (pin "4") (pinfunction "VSENSE_4") (pintype "passive"))
      (node (ref "J15") (pin "1") (pinfunction "1_1") (pintype "passive"))
      (node (ref "R4") (pin "2") (pinfunction "2_2") (pintype "passive"))
    )
    (net (code "22") (name "Net-(IC2-BOOT)") (class "Default")
      (node (ref "C11") (pin "1") (pinfunction "1_1") (pintype "passive"))
      (node (ref "IC2") (pin "1") (pinfunction "BOOT_1") (pintype "passive"))
    )
    (net (code "23") (name "Net-(IC2-VIN)") (class "Default")
      (node (ref "C15") (pin "1") (pinfunction "1_1") (pintype "passive"))
      (node (ref "C16") (pin "1") (pinfunction "1_1") (pintype "passive"))
      (node (ref "C17") (pin "1") (pinfunction "1_1") (pintype "passive"))
      (node (ref "IC2") (pin "7") (pinfunction "VIN_7") (pintype "passive"))
      (node (ref "S2") (pin "3") (pinfunction "N.C._3") (pintype "passive"))
    )
    (net (code "24") (name "Net-(IC2-VSENSE)") (class "Default")
      (node (ref "IC2") (pin "4") (pinfunction "VSENSE_4") (pintype "passive"))
      (node (ref "J16") (pin "1") (pinfunction "1_1") (pintype "passive"))
      (node (ref "R7") (pin "2") (pinfunction "2_2") (pintype "passive"))
    )
    (net (code "25") (name "Net-(IC3-BOOT)") (class "Default")
      (node (ref "C19") (pin "1") (pinfunction "1_1") (pintype "passive"))
      (node (ref "IC3") (pin "1") (pinfunction "BOOT_1") (pintype "passive"))
    )
    (net (code "26") (name "Net-(IC3-VIN)") (class "Default")
      (node (ref "C23") (pin "1") (pinfunction "1_1") (pintype "passive"))
      (node (ref "C24") (pin "1") (pinfunction "1_1") (pintype "passive"))
      (node (ref "C25") (pin "1") (pinfunction "1_1") (pintype "passive"))
      (node (ref "IC3") (pin "7") (pinfunction "VIN_7") (pintype "passive"))
      (node (ref "S3") (pin "3") (pinfunction "N.C._3") (pintype "passive"))
    )
    (net (code "27") (name "Net-(IC3-VSENSE)") (class "Default")
      (node (ref "IC3") (pin "4") (pinfunction "VSENSE_4") (pintype "passive"))
      (node (ref "J17") (pin "1") (pinfunction "1_1") (pintype "passive"))
      (node (ref "R10") (pin "2") (pinfunction "2_2") (pintype "passive"))
    )
    (net (code "28") (name "Net-(IC4-BOOT)") (class "Default")
      (node (ref "C27") (pin "1") (pinfunction "1_1") (pintype "passive"))
      (node (ref "IC4") (pin "1") (pinfunction "BOOT_1") (pintype "passive"))
    )
    (net (code "29") (name "Net-(IC4-VIN)") (class "Default")
      (node (ref "C31") (pin "1") (pinfunction "1_1") (pintype "passive"))
      (node (ref "C32") (pin "1") (pinfunction "1_1") (pintype "passive"))
      (node (ref "C33") (pin "1") (pinfunction "1_1") (pintype "passive"))
      (node (ref "IC4") (pin "7") (pinfunction "VIN_7") (pintype "passive"))
      (node (ref "S4") (pin "3") (pinfunction "N.C._3") (pintype "passive"))
    )
    (net (code "30") (name "Net-(IC4-VSENSE)") (class "Default")
      (node (ref "IC4") (pin "4") (pinfunction "VSENSE_4") (pintype "passive"))
      (node (ref "J18") (pin "1") (pinfunction "1_1") (pintype "passive"))
      (node (ref "R13") (pin "2") (pinfunction "2_2") (pintype "passive"))
    )
    (net (code "31") (name "Net-(LED2-A)") (class "Default")
      (node (ref "LED2") (pin "2") (pinfunction "A_2") (pintype "passive"))
      (node (ref "R5") (pin "2") (pinfunction "2_2") (pintype "passive"))
    )
    (net (code "32") (name "Net-(LED3-A)") (class "Default")
      (node (ref "LED3") (pin "2") (pinfunction "A_2") (pintype "passive"))
      (node (ref "R8") (pin "2") (pinfunction "2_2") (pintype "passive"))
    )
    (net (code "33") (name "Net-(LED4-A)") (class "Default")
      (node (ref "LED4") (pin "2") (pinfunction "A_2") (pintype "passive"))
      (node (ref "R11") (pin "2") (pinfunction "2_2") (pintype "passive"))
    )
    (net (code "34") (name "Net-(LED5-A)") (class "Default")
      (node (ref "LED5") (pin "2") (pinfunction "A_2") (pintype "passive"))
      (node (ref "R14") (pin "2") (pinfunction "2_2") (pintype "passive"))
    )
    (net (code "35") (name "VAR1") (class "Default")
      (node (ref "C4") (pin "1") (pinfunction "+_1") (pintype "passive"))
      (node (ref "C6") (pin "1") (pinfunction "1_1") (pintype "passive"))
      (node (ref "F1") (pin "1") (pinfunction "1_1") (pintype "passive"))
      (node (ref "L1") (pin "2") (pinfunction "2_2") (pintype "passive"))
      (node (ref "R4") (pin "1") (pinfunction "1_1") (pintype "passive"))
    )
    (net (code "36") (name "VAR2") (class "Default")
      (node (ref "C12") (pin "1") (pinfunction "+_1") (pintype "passive"))
      (node (ref "C14") (pin "1") (pinfunction "1_1") (pintype "passive"))
      (node (ref "F2") (pin "1") (pinfunction "1_1") (pintype "passive"))
      (node (ref "L2") (pin "2") (pinfunction "2_2") (pintype "passive"))
      (node (ref "R7") (pin "1") (pinfunction "1_1") (pintype "passive"))
    )
    (net (code "37") (name "VAR3") (class "Default")
      (node (ref "C20") (pin "1") (pinfunction "+_1") (pintype "passive"))
      (node (ref "C22") (pin "1") (pinfunction "1_1") (pintype "passive"))
      (node (ref "F3") (pin "1") (pinfunction "1_1") (pintype "passive"))
      (node (ref "L3") (pin "2") (pinfunction "2_2") (pintype "passive"))
      (node (ref "R10") (pin "1") (pinfunction "1_1") (pintype "passive"))
    )
    (net (code "38") (name "VAR4") (class "Default")
      (node (ref "C28") (pin "1") (pinfunction "+_1") (pintype "passive"))
      (node (ref "C30") (pin "1") (pinfunction "1_1") (pintype "passive"))
      (node (ref "F4") (pin "1") (pinfunction "1_1") (pintype "passive"))
      (node (ref "L4") (pin "2") (pinfunction "2_2") (pintype "passive"))
      (node (ref "R13") (pin "1") (pinfunction "1_1") (pintype "passive"))
    )
    (net (code "39") (name "unconnected-(IC1-ENA-Pad5)") (class "Default")
      (node (ref "IC1") (pin "5") (pinfunction "ENA_5") (pintype "passive+no_connect"))
    )
    (net (code "40") (name "unconnected-(IC1-NC_1-Pad2)") (class "Default")
      (node (ref "IC1") (pin "2") (pinfunction "NC_1_2") (pintype "passive+no_connect"))
    )
    (net (code "41") (name "unconnected-(IC1-NC_2-Pad3)") (class "Default")
      (node (ref "IC1") (pin "3") (pinfunction "NC_2_3") (pintype "passive+no_connect"))
    )
    (net (code "42") (name "unconnected-(IC2-ENA-Pad5)") (class "Default")
      (node (ref "IC2") (pin "5") (pinfunction "ENA_5") (pintype "passive+no_connect"))
    )
    (net (code "43") (name "unconnected-(IC2-NC_1-Pad2)") (class "Default")
      (node (ref "IC2") (pin "2") (pinfunction "NC_1_2") (pintype "passive+no_connect"))
    )
    (net (code "44") (name "unconnected-(IC2-NC_2-Pad3)") (class "Default")
      (node (ref "IC2") (pin "3") (pinfunction "NC_2_3") (pintype "passive+no_connect"))
    )
    (net (code "45") (name "unconnected-(IC3-ENA-Pad5)") (class "Default")
      (node (ref "IC3") (pin "5") (pinfunction "ENA_5") (pintype "passive+no_connect"))
    )
    (net (code "46") (name "unconnected-(IC3-NC_1-Pad2)") (class "Default")
      (node (ref "IC3") (pin "2") (pinfunction "NC_1_2") (pintype "passive+no_connect"))
    )
    (net (code "47") (name "unconnected-(IC3-NC_2-Pad3)") (class "Default")
      (node (ref "IC3") (pin "3") (pinfunction "NC_2_3") (pintype "passive+no_connect"))
    )
    (net (code "48") (name "unconnected-(IC4-ENA-Pad5)") (class "Default")
      (node (ref "IC4") (pin "5") (pinfunction "ENA_5") (pintype "passive+no_connect"))
    )
    (net (code "49") (name "unconnected-(IC4-NC_1-Pad2)") (class "Default")
      (node (ref "IC4") (pin "2") (pinfunction "NC_1_2") (pintype "passive+no_connect"))
    )
    (net (code "50") (name "unconnected-(IC4-NC_2-Pad3)") (class "Default")
      (node (ref "IC4") (pin "3") (pinfunction "NC_2_3") (pintype "passive+no_connect"))
    )
    (net (code "51") (name "unconnected-(S1-NOT_CONNECECTED-Pad1)") (class "Default")
      (node (ref "S1") (pin "1") (pinfunction "NOT_CONNECECTED_1") (pintype "passive+no_connect"))
    )
    (net (code "52") (name "unconnected-(S2-NOT_CONNECECTED-Pad1)") (class "Default")
      (node (ref "S2") (pin "1") (pinfunction "NOT_CONNECECTED_1") (pintype "passive+no_connect"))
    )
    (net (code "53") (name "unconnected-(S3-NOT_CONNECECTED-Pad1)") (class "Default")
      (node (ref "S3") (pin "1") (pinfunction "NOT_CONNECECTED_1") (pintype "passive+no_connect"))
    )
    (net (code "54") (name "unconnected-(S4-NOT_CONNECECTED-Pad1)") (class "Default")
      (node (ref "S4") (pin "1") (pinfunction "NOT_CONNECECTED_1") (pintype "passive+no_connect"))
    )
  )
)
